# Voltage_Control.net
KiCad netlist of a schematic drawn in Altium Designer
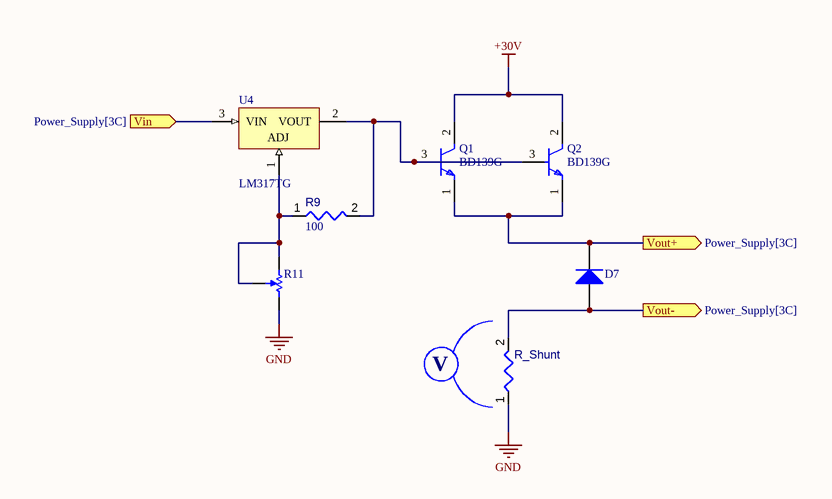
[diagram p0: Voltage_Control.SchDoc]

(export (version "E")
  (design (tool "Eeschema 10.0.6"))
  (components
    (comp (ref "D7")
      (value "1N4007")
      (footprint "FAIR-DO-41-2")
      (description "General Purpose Rectifier, 1.1 V, 1.0 A, -55 to 175 degC, 2-Pin DO-41, RoHS, Tape and Reel")
      (fields (field (name "MANUFACTURER") "Fairchild"))
      (libsource (lib "Konstantinos Psarras") (part "KESE-D_K1A2-2"))
    )
    (comp (ref "Q1")
      (value "BD139G")
      (footprint "FP-77-09-MFG")
      (description "1.5 A, 80 V NPN Power Bipolar Junction Transistor. ONSSPCTRNSTLT1T0R;")
      (libsource (lib "Konstantinos Psarras") (part "2239aae8d27e6eb6063ebea98827daf"))
    )
    (comp (ref "Q2")
      (value "BD139G")
      (footprint "FP-77-09-MFG")
      (description "1.5 A, 80 V NPN Power Bipolar Junction Transistor. ONSSPCTRNSTLT1T0R;")
      (libsource (lib "Konstantinos Psarras") (part "2239aae8d27e6eb6063ebea98827daf"))
    )
    (comp (ref "R9")
      (value "100")
      (footprint "RESA60-630X240")
      (description "Axial Resistor, 100 Ohm, +/- 1%, 0.25 W, -55 to 155 degC, 2-Pin THD, RoHS, Bulk")
      (fields (field (name "POWER") "250mW") (field (name "TOLERANCE") "1%"))
      (libsource (lib "Konstantinos Psarras") (part "RES-2"))
    )
    (comp (ref "R11")
      (value "3296W-1-102LF")
      (footprint "BOUR-3296W-1-3")
      (description "Square Trimpot(R) Trimming Potentiometer, 1000 Ohm, -55 to 125 degC, 3-Pin THD, RoHS, Tube")
      (fields (field (name "MANUFACTURER") "Bourns") (field (name "POWER") "500mW"))
      (libsource (lib "Konstantinos Psarras") (part "RES-ADJ-3"))
    )
    (comp (ref "R_Shunt")
      (value "MFR-25FBF52-100R")
      (footprint "RESA60-630X240")
      (description "Axial Resistor, 100 Ohm, +/- 1%, 0.25 W, -55 to 155 degC, 2-Pin THD, RoHS, Bulk")
      (fields (field (name "POWER") "250mW") (field (name "TOLERANCE") "1%"))
      (libsource (lib "Konstantinos Psarras") (part "RES-2"))
    )
    (comp (ref "U4")
      (value "LM317TG")
      (footprint "ONSC-TO-220-3-221AB-01")
      (fields (field (name "MANUFACTURER") "ON Semiconductor"))
      (libsource (lib "Konstantinos Psarras") (part "ONSC-LM317TG-3"))
    )
  )
  (nets
    (net (code "1") (name "+30V") (class "Default")
      (node (ref "Q1") (pin "2") (pinfunction "C_2") (pintype "passive"))
      (node (ref "Q2") (pin "2") (pinfunction "C_2") (pintype "passive"))
    )
    (net (code "2") (name "/Vin") (class "Default")
      (node (ref "U4") (pin "3") (pinfunction "VIN_3") (pintype "input"))
    )
    (net (code "3") (name "/Vout+") (class "Default")
      (node (ref "D7") (pin "1") (pinfunction "K_1") (pintype "passive"))
      (node (ref "Q1") (pin "1") (pinfunction "E_1") (pintype "passive"))
      (node (ref "Q2") (pin "1") (pinfunction "E_1") (pintype "passive"))
    )
    (net (code "4") (name "/Vout-") (class "Default")
      (node (ref "D7") (pin "2") (pinfunction "A_2") (pintype "passive"))
      (node (ref "R_Shunt") (pin "2") (pinfunction "2_2") (pintype "passive"))
    )
    (net (code "5") (name "GND") (class "Default")
      (node (ref "R11") (pin "2") (pinfunction "B_2") (pintype "passive"))
      (node (ref "R_Shunt") (pin "1") (pinfunction "1_1") (pintype "passive"))
    )
    (net (code "6") (name "Net-(Q1-B)") (class "Default")
      (node (ref "Q1") (pin "3") (pinfunction "B_3") (pintype "passive"))
      (node (ref "Q2") (pin "3") (pinfunction "B_3") (pintype "passive"))
      (node (ref "R9") (pin "2") (pinfunction "2_2") (pintype "passive"))
      (node (ref "U4") (pin "2") (pinfunction "VOUT_2") (pintype "power_in"))
    )
    (net (code "7") (name "Net-(R11-A)") (class "Default")
      (node (ref "R11") (pin "1") (pinfunction "A_1") (pintype "passive"))
      (node (ref "R11") (pin "3") (pinfunction "TAP_3") (pintype "passive"))
      (node (ref "R9") (pin "1") (pinfunction "1_1") (pintype "passive"))
      (node (ref "U4") (pin "1") (pinfunction "ADJ_1") (pintype "input"))
    )
  )
)
